# VS1000.net
KiCad netlist of a schematic drawn in EAGLE
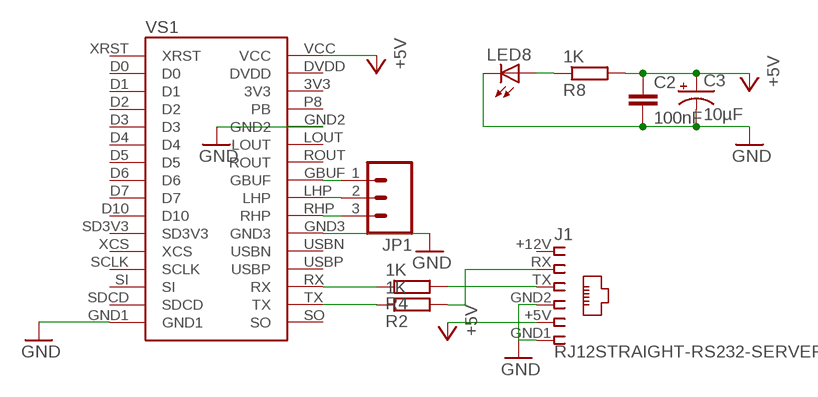
[diagram p0: schematic, sheet 1]

(export (version "E")
  (design (tool "Eeschema 10.0.6"))
  (components
    (comp (ref "C2")
      (value "100nF")
      (footprint "eagle-import:C1206")
      (libsource (lib "eagle-import") (part "C-EUC1206"))
    )
    (comp (ref "C3")
      (value "10µF")
      (footprint "eagle-import:EIA3216")
      (libsource (lib "eagle-import") (part "CAP_POL1206"))
    )
    (comp (ref "J1")
      (value "RJ12STRAIGHT-RS232-SERVER")
      (footprint "eagle-import:RJ12-STRAIGHT-RS232")
      (libsource (lib "eagle-import") (part "RJ12STRAIGHT-RS232-SERVER"))
    )
    (comp (ref "JP1")
      (value "M03LONGPADS")
      (footprint "eagle-import:1X03_LONGPADS")
      (libsource (lib "eagle-import") (part "M03LONGPADS"))
    )
    (comp (ref "LED8")
      (value "LED3MM")
      (footprint "eagle-import:LED3MM")
      (libsource (lib "eagle-import") (part "LED3MM"))
    )
    (comp (ref "R2")
      (value "1K")
      (footprint "eagle-import:M1206")
      (libsource (lib "eagle-import") (part "R-EU_M1206"))
    )
    (comp (ref "R4")
      (value "1K")
      (footprint "eagle-import:M1206")
      (libsource (lib "eagle-import") (part "R-EU_M1206"))
    )
    (comp (ref "R8")
      (value "1K")
      (footprint "eagle-import:M1206")
      (libsource (lib "eagle-import") (part "R-EU_M1206"))
    )
    (comp (ref "VS1")
      (value "VS1000")
      (footprint "eagle-import:VS1000")
      (libsource (lib "eagle-import") (part "VS1000"))
    )
  )
  (nets
    (net (code "1") (name "+5V") (class "Default")
      (node (ref "C2") (pin "1") (pinfunction "1_1") (pintype "passive"))
      (node (ref "C3") (pin "A") (pinfunction "+_A") (pintype "passive"))
      (node (ref "J1") (pin "+5V") (pinfunction "5_+5V") (pintype "power_in"))
      (node (ref "R8") (pin "2") (pinfunction "2_2") (pintype "passive"))
      (node (ref "VS1") (pin "VCC") (pinfunction "VCC_VCC") (pintype "bidirectional"))
    )
    (net (code "2") (name "/1") (class "Default")
      (node (ref "J1") (pin "+12V") (pinfunction "1_+12V") (pintype "power_in"))
    )
    (net (code "3") (name "/SCLK") (class "Default")
      (node (ref "VS1") (pin "SCLK") (pinfunction "SCLK_SCLK") (pintype "power_in"))
    )
    (net (code "4") (name "/SD3V3") (class "Default")
      (node (ref "VS1") (pin "SD3V3") (pinfunction "SD3V3_SD3V3") (pintype "power_in"))
    )
    (net (code "5") (name "/SI") (class "Default")
      (node (ref "VS1") (pin "SI") (pinfunction "SI_SI") (pintype "power_in"))
    )
    (net (code "6") (name "/XCS") (class "Default")
      (node (ref "VS1") (pin "XCS") (pinfunction "XCS_XCS") (pintype "power_in"))
    )
    (net (code "7") (name "GND") (class "Default")
      (node (ref "C2") (pin "2") (pinfunction "2_2") (pintype "passive"))
      (node (ref "C3") (pin "C") (pinfunction "-_C") (pintype "passive"))
      (node (ref "J1") (pin "GND1") (pinfunction "6_GND1") (pintype "power_in"))
      (node (ref "J1") (pin "GND2") (pinfunction "4_GND2") (pintype "power_in"))
      (node (ref "LED8") (pin "K") (pinfunction "C_K") (pintype "passive"))
      (node (ref "VS1") (pin "GND1") (pinfunction "GND1_GND1") (pintype "bidirectional"))
      (node (ref "VS1") (pin "GND2") (pinfunction "GND2_GND2") (pintype "bidirectional"))
      (node (ref "VS1") (pin "GND3") (pinfunction "GND3_GND3") (pintype "bidirectional"))
    )
    (net (code "8") (name "Net-(J1-2)") (class "Default")
      (node (ref "J1") (pin "RX") (pinfunction "2_RX") (pintype "bidirectional"))
      (node (ref "R2") (pin "2") (pinfunction "2_2") (pintype "passive"))
    )
    (net (code "9") (name "Net-(J1-3)") (class "Default")
      (node (ref "J1") (pin "TX") (pinfunction "3_TX") (pintype "bidirectional"))
      (node (ref "R4") (pin "2") (pinfunction "2_2") (pintype "passive"))
    )
    (net (code "10") (name "Net-(JP1-Pad1)") (class "Default")
      (node (ref "JP1") (pin "1") (pinfunction "1_1") (pintype "passive"))
      (node (ref "VS1") (pin "GBUF") (pinfunction "GBUF_GBUF") (pintype "bidirectional"))
    )
    (net (code "11") (name "Net-(JP1-Pad2)") (class "Default")
      (node (ref "JP1") (pin "2") (pinfunction "2_2") (pintype "passive"))
      (node (ref "VS1") (pin "LHP") (pinfunction "LHP_LHP") (pintype "bidirectional"))
    )
    (net (code "12") (name "Net-(JP1-Pad3)") (class "Default")
      (node (ref "JP1") (pin "3") (pinfunction "3_3") (pintype "passive"))
      (node (ref "VS1") (pin "RHP") (pinfunction "RHP_RHP") (pintype "bidirectional"))
    )
    (net (code "13") (name "Net-(LED8-PadA)") (class "Default")
      (node (ref "LED8") (pin "A") (pinfunction "A_A") (pintype "passive"))
      (node (ref "R8") (pin "1") (pinfunction "1_1") (pintype "passive"))
    )
    (net (code "14") (name "Net-(R2-Pad1)") (class "Default")
      (node (ref "R2") (pin "1") (pinfunction "1_1") (pintype "passive"))
      (node (ref "VS1") (pin "TX") (pinfunction "TX_TX") (pintype "bidirectional"))
    )
    (net (code "15") (name "Net-(R4-Pad1)") (class "Default")
      (node (ref "R4") (pin "1") (pinfunction "1_1") (pintype "passive"))
      (node (ref "VS1") (pin "RX") (pinfunction "RX_RX") (pintype "bidirectional"))
    )
    (net (code "16") (name "unconnected-(VS1-PB-PadP8)") (class "Default")
      (node (ref "VS1") (pin "P8") (pinfunction "PB_P8") (pintype "bidirectional"))
    )
    (net (code "17") (name "unconnected-(VS1-Pad3V3)") (class "Default")
      (node (ref "VS1") (pin "3V3") (pinfunction "3V3_3V3") (pintype "bidirectional"))
    )
    (net (code "18") (name "unconnected-(VS1-PadD0)") (class "Default")
      (node (ref "VS1") (pin "D0") (pinfunction "D0_D0") (pintype "bidirectional"))
    )
    (net (code "19") (name "unconnected-(VS1-PadD1)") (class "Default")
      (node (ref "VS1") (pin "D1") (pinfunction "D1_D1") (pintype "bidirectional"))
    )
    (net (code "20") (name "unconnected-(VS1-PadD2)") (class "Default")
      (node (ref "VS1") (pin "D2") (pinfunction "D2_D2") (pintype "bidirectional"))
    )
    (net (code "21") (name "unconnected-(VS1-PadD3)") (class "Default")
      (node (ref "VS1") (pin "D3") (pinfunction "D3_D3") (pintype "bidirectional"))
    )
    (net (code "22") (name "unconnected-(VS1-PadD4)") (class "Default")
      (node (ref "VS1") (pin "D4") (pinfunction "D4_D4") (pintype "bidirectional"))
    )
    (net (code "23") (name "unconnected-(VS1-PadD5)") (class "Default")
      (node (ref "VS1") (pin "D5") (pinfunction "D5_D5") (pintype "bidirectional"))
    )
    (net (code "24") (name "unconnected-(VS1-PadD6)") (class "Default")
      (node (ref "VS1") (pin "D6") (pinfunction "D6_D6") (pintype "bidirectional"))
    )
    (net (code "25") (name "unconnected-(VS1-PadD7)") (class "Default")
      (node (ref "VS1") (pin "D7") (pinfunction "D7_D7") (pintype "bidirectional"))
    )
    (net (code "26") (name "unconnected-(VS1-PadD10)") (class "Default")
      (node (ref "VS1") (pin "D10") (pinfunction "D10_D10") (pintype "bidirectional"))
    )
    (net (code "27") (name "unconnected-(VS1-PadDVDD)") (class "Default")
      (node (ref "VS1") (pin "DVDD") (pinfunction "DVDD_DVDD") (pintype "bidirectional"))
    )
    (net (code "28") (name "unconnected-(VS1-PadLOUT)") (class "Default")
      (node (ref "VS1") (pin "LOUT") (pinfunction "LOUT_LOUT") (pintype "bidirectional"))
    )
    (net (code "29") (name "unconnected-(VS1-PadROUT)") (class "Default")
      (node (ref "VS1") (pin "ROUT") (pinfunction "ROUT_ROUT") (pintype "bidirectional"))
    )
    (net (code "30") (name "unconnected-(VS1-PadSDCD)") (class "Default")
      (node (ref "VS1") (pin "SDCD") (pinfunction "SDCD_SDCD") (pintype "bidirectional"))
    )
    (net (code "31") (name "unconnected-(VS1-PadSO)") (class "Default")
      (node (ref "VS1") (pin "SO") (pinfunction "SO_SO") (pintype "bidirectional"))
    )
    (net (code "32") (name "unconnected-(VS1-PadUSBN)") (class "Default")
      (node (ref "VS1") (pin "USBN") (pinfunction "USBN_USBN") (pintype "bidirectional"))
    )
    (net (code "33") (name "unconnected-(VS1-PadUSBP)") (class "Default")
      (node (ref "VS1") (pin "USBP") (pinfunction "USBP_USBP") (pintype "bidirectional"))
    )
    (net (code "34") (name "unconnected-(VS1-PadXRST)") (class "Default")
      (node (ref "VS1") (pin "XRST") (pinfunction "XRST_XRST") (pintype "bidirectional"))
    )
  )
)
